# temperature.net
KiCad netlist of a schematic drawn in Altium Designer
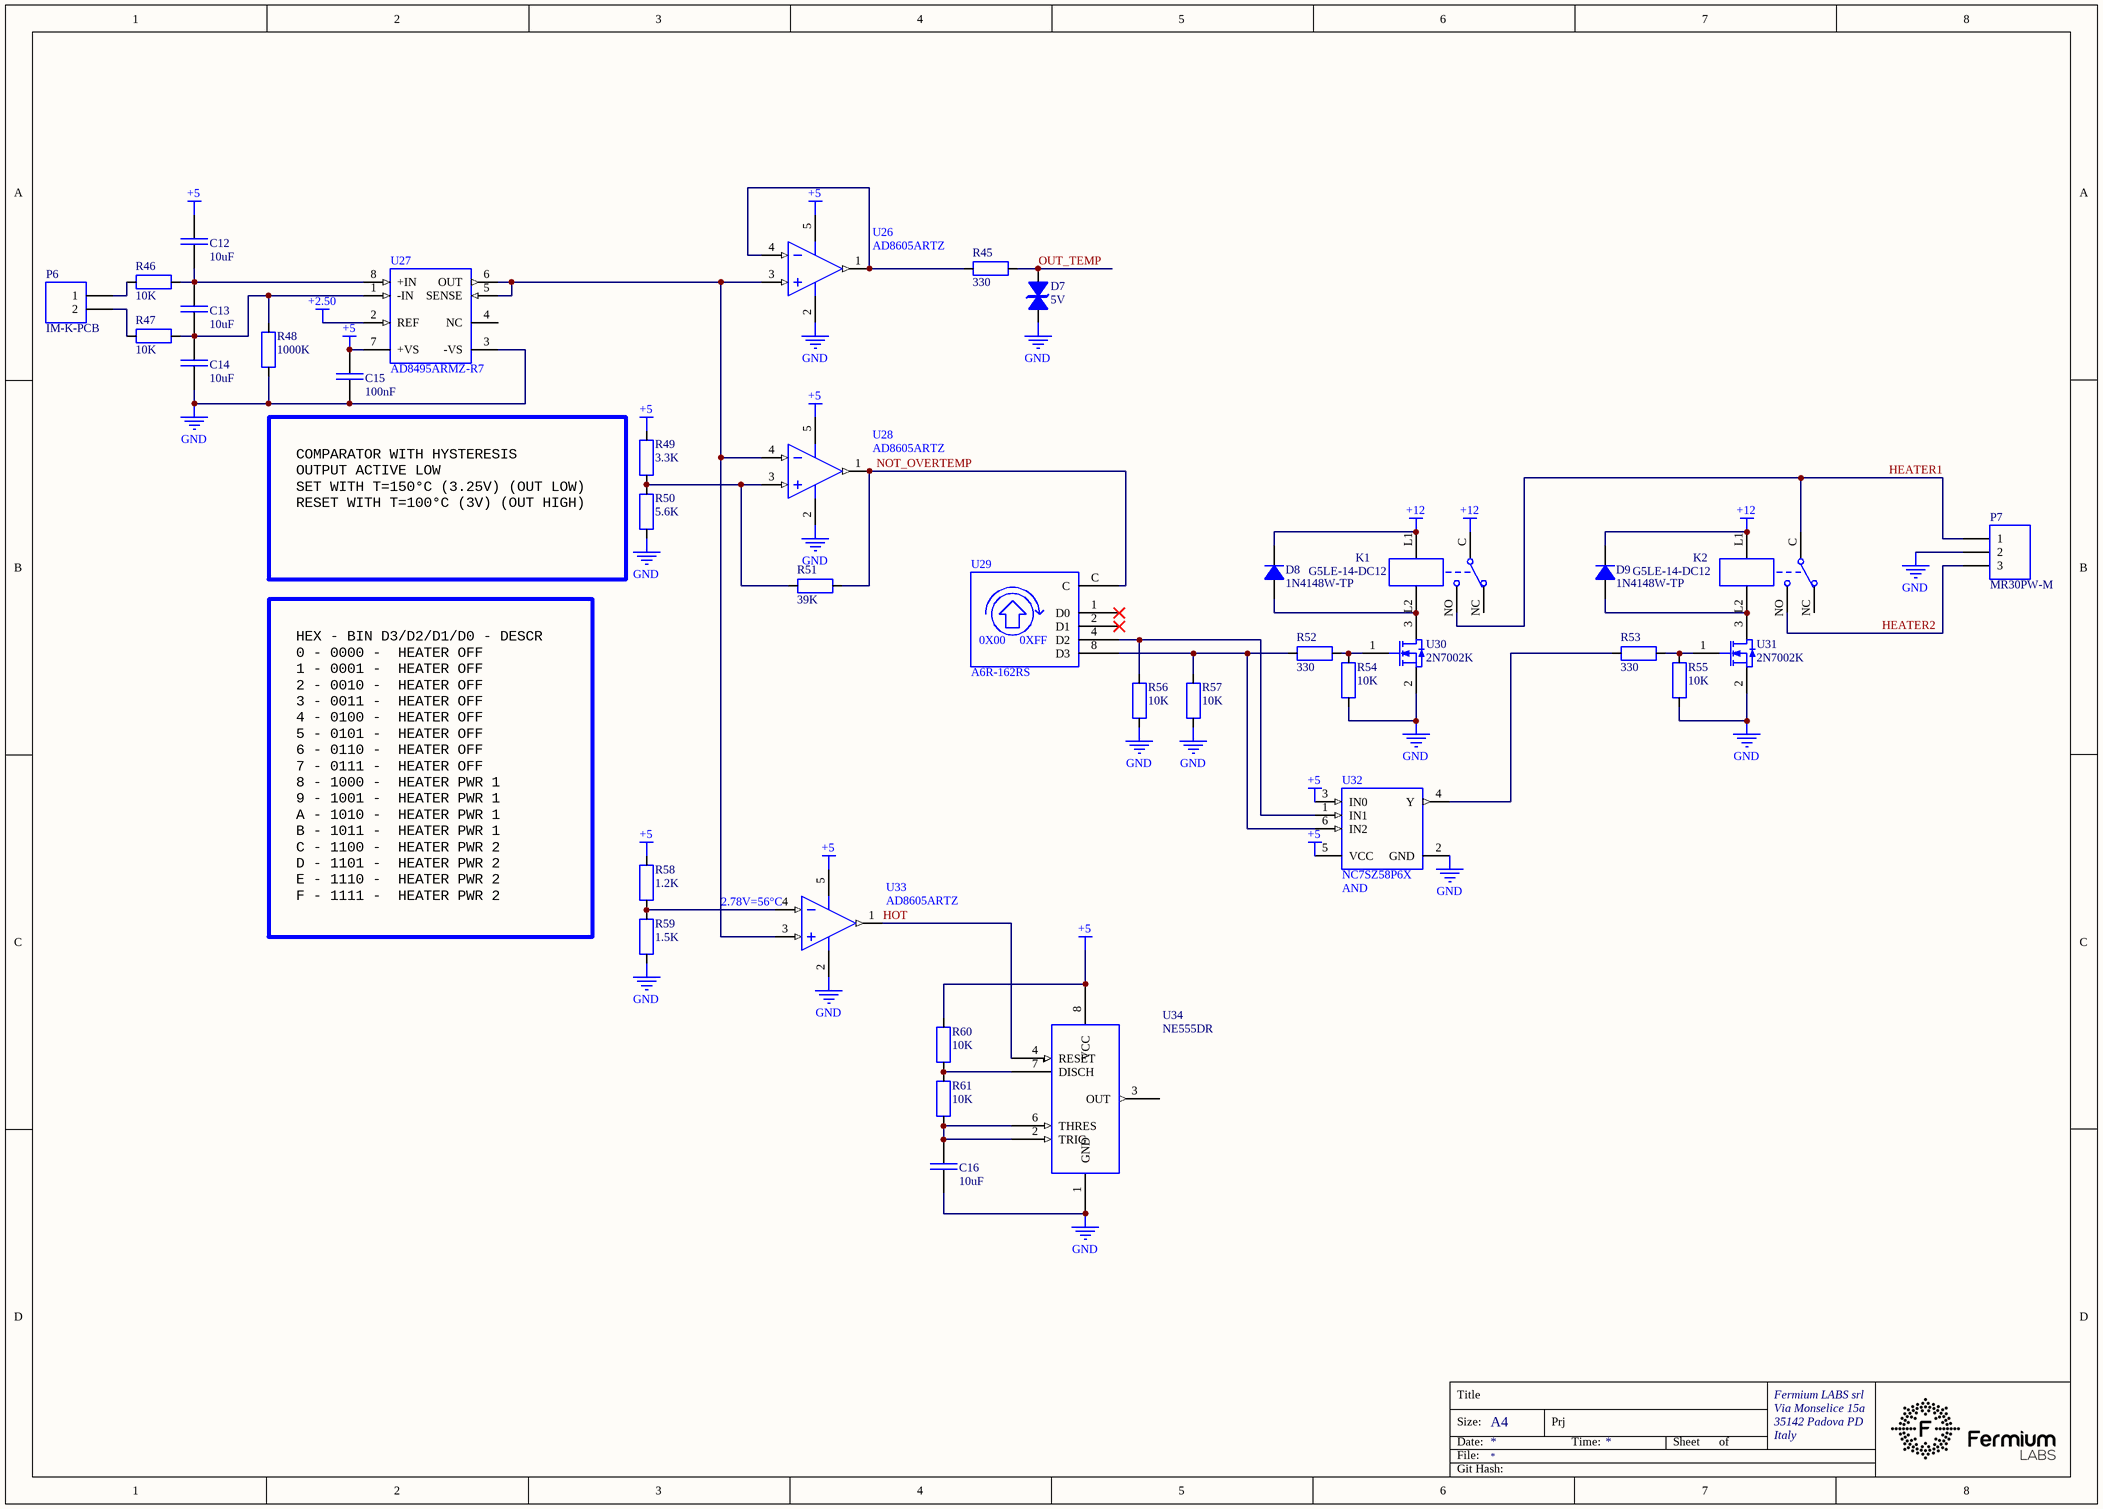
[diagram p0: temperature.SchDoc]

(export (version "E")
  (design (tool "Eeschema 10.0.6"))
  (components
    (comp (ref "C12")
      (value "10uF")
      (footprint "CAP 0805_2012")
      (description "CAP SMD MLCC 10uF 25V 0805 X5R")
      (fields (field (name "PART NUMBER") "1ffbe5a9-0884-4740-bdad-20a6a98400e6"))
      (libsource (lib "frmdblib") (part "GENERIC_C"))
    )
    (comp (ref "C13")
      (value "10uF")
      (footprint "CAP 0805_2012")
      (description "CAP SMD MLCC 10uF 25V 0805 X5R")
      (fields (field (name "PART NUMBER") "1ffbe5a9-0884-4740-bdad-20a6a98400e6"))
      (libsource (lib "frmdblib") (part "GENERIC_C"))
    )
    (comp (ref "C14")
      (value "10uF")
      (footprint "CAP 0805_2012")
      (description "CAP SMD MLCC 10uF 25V 0805 X5R")
      (fields (field (name "PART NUMBER") "1ffbe5a9-0884-4740-bdad-20a6a98400e6"))
      (libsource (lib "frmdblib") (part "GENERIC_C"))
    )
    (comp (ref "C15")
      (value "100nF")
      (footprint "CAP 0603_1608")
      (description "CAP SMD MLCC 100nF 25V 0603 X7R")
      (fields (field (name "PART NUMBER") "02841f84-ac15-41b5-9e17-915f8f067828"))
      (libsource (lib "frmdblib") (part "GENERIC_C"))
    )
    (comp (ref "C16")
      (value "10uF")
      (footprint "CAP 0805_2012")
      (description "CAP SMD MLCC 10uF 25V 0805 X5R")
      (fields (field (name "PART NUMBER") "1ffbe5a9-0884-4740-bdad-20a6a98400e6"))
      (libsource (lib "frmdblib") (part "GENERIC_C"))
    )
    (comp (ref "D7")
      (value "5V")
      (footprint "SOD523F")
      (description "DIODE SMD TVS 5V BIDIRECTIONAL SOD-523")
      (fields (field (name "PART NUMBER") "daa58212-38e2-4326-a156-8e48058c46f1"))
      (libsource (lib "frmdblib") (part "GENERIC_D_TVS_BI"))
    )
    (comp (ref "D8")
      (value "1N4148W-TP")
      (footprint "SOD-123")
      (description "DIODE SMD 100V 150mA 1.5Vf SOD-123 4148")
      (fields (field (name "PART NUMBER") "5e920700-75df-48e3-84dd-8f9f777caed8"))
      (libsource (lib "frmdblib") (part "GENERIC_D"))
    )
    (comp (ref "D9")
      (value "1N4148W-TP")
      (footprint "SOD-123")
      (description "DIODE SMD 100V 150mA 1.5Vf SOD-123 4148")
      (fields (field (name "PART NUMBER") "5e920700-75df-48e3-84dd-8f9f777caed8"))
      (libsource (lib "frmdblib") (part "GENERIC_D"))
    )
    (comp (ref "K1")
      (value "G5LE-14-DC12")
      (footprint "AAE46D0F-8D2F-4914-8614-C04E242B4758")
      (description "RELAY SPDT 10A 250VAC 12VDC SUBMINIATURE")
      (fields (field (name "PART NUMBER") "daf6f3cd-58c4-4886-bcb7-b7b47a76ae08"))
      (libsource (lib "frmdblib") (part "GENERIC_RELAY_SPDT"))
    )
    (comp (ref "K2")
      (value "G5LE-14-DC12")
      (footprint "AAE46D0F-8D2F-4914-8614-C04E242B4758")
      (description "RELAY SPDT 10A 250VAC 12VDC SUBMINIATURE")
      (fields (field (name "PART NUMBER") "daf6f3cd-58c4-4886-bcb7-b7b47a76ae08"))
      (libsource (lib "frmdblib") (part "GENERIC_RELAY_SPDT"))
    )
    (comp (ref "P6")
      (value "IM-K-PCB")
      (footprint "9044FB30-693E-4780-9B0B-95C5421D70E8")
      (description "CONN THERMOCOUPLE K-TYPE THT")
      (fields (field (name "PART NUMBER") "44088476-53fa-4578-a611-1fd63affe7b4"))
      (libsource (lib "frmdblib") (part "Header 2"))
    )
    (comp (ref "P7")
      (value "MR30PW-M")
      (footprint "B3F23392-877C-4EEC-B1AF-B260E8D92153")
      (description "CONN DC 3 POLE 15A PCB MALE")
      (fields (field (name "PART NUMBER") "8565bfd1-7a71-455a-a363-4ce9dda60de6"))
      (libsource (lib "frmdblib") (part "Header 3"))
    )
    (comp (ref "R45")
      (value "330")
      (description "RES SMD 330 OHM 1% 1/10W 0603")
      (fields (field (name "PART NUMBER") "e8555d7b-eeda-4727-b2e1-550cdc03d819"))
      (libsource (lib "frmdblib") (part "GENERIC_R"))
    )
    (comp (ref "R46")
      (value "10K")
      (footprint "RES 0603_1608")
      (description "RES SMD 10K OHM 1% 1/10W 0603")
      (fields (field (name "PART NUMBER") "93242766-ba1d-462d-b58f-ce1dfc4129c8"))
      (libsource (lib "frmdblib") (part "GENERIC_R"))
    )
    (comp (ref "R47")
      (value "10K")
      (footprint "RES 0603_1608")
      (description "RES SMD 10K OHM 1% 1/10W 0603")
      (fields (field (name "PART NUMBER") "93242766-ba1d-462d-b58f-ce1dfc4129c8"))
      (libsource (lib "frmdblib") (part "GENERIC_R"))
    )
    (comp (ref "R48")
      (value "1000K")
      (description "RES SMD 1000K OHM 1% 1/8W 0805")
      (fields (field (name "PART NUMBER") "971a2486-fdc6-42b3-9467-9814f305537f"))
      (libsource (lib "frmdblib") (part "GENERIC_R"))
    )
    (comp (ref "R49")
      (value "3.3K")
      (description "RES SMD 3.3K OHM 1% 1/10W 0603")
      (fields (field (name "PART NUMBER") "c685e076-af25-4fed-81c8-3eb7c43f01b8"))
      (libsource (lib "frmdblib") (part "GENERIC_R"))
    )
    (comp (ref "R50")
      (value "5.6K")
      (description "RES SMD 5.6K OHM 1% 1/10W 0603")
      (fields (field (name "PART NUMBER") "afc45e5f-a770-4ee7-b734-99356076b47f"))
      (libsource (lib "frmdblib") (part "GENERIC_R"))
    )
    (comp (ref "R51")
      (value "39K")
      (description "RES SMD 39K OHM 1% 1/10W 0603")
      (fields (field (name "PART NUMBER") "10a824dc-98f1-41df-91f2-219e0508d035"))
      (libsource (lib "frmdblib") (part "GENERIC_R"))
    )
    (comp (ref "R52")
      (value "330")
      (description "RES SMD 330 OHM 1% 1/10W 0603")
      (fields (field (name "PART NUMBER") "e8555d7b-eeda-4727-b2e1-550cdc03d819"))
      (libsource (lib "frmdblib") (part "GENERIC_R"))
    )
    (comp (ref "R53")
      (value "330")
      (description "RES SMD 330 OHM 1% 1/10W 0603")
      (fields (field (name "PART NUMBER") "e8555d7b-eeda-4727-b2e1-550cdc03d819"))
      (libsource (lib "frmdblib") (part "GENERIC_R"))
    )
    (comp (ref "R54")
      (value "10K")
      (footprint "RES 0603_1608")
      (description "RES SMD 10K OHM 1% 1/10W 0603")
      (fields (field (name "PART NUMBER") "93242766-ba1d-462d-b58f-ce1dfc4129c8"))
      (libsource (lib "frmdblib") (part "GENERIC_R"))
    )
    (comp (ref "R55")
      (value "10K")
      (footprint "RES 0603_1608")
      (description "RES SMD 10K OHM 1% 1/10W 0603")
      (fields (field (name "PART NUMBER") "93242766-ba1d-462d-b58f-ce1dfc4129c8"))
      (libsource (lib "frmdblib") (part "GENERIC_R"))
    )
    (comp (ref "R56")
      (value "10K")
      (footprint "RES 0603_1608")
      (description "RES SMD 10K OHM 1% 1/10W 0603")
      (fields (field (name "PART NUMBER") "93242766-ba1d-462d-b58f-ce1dfc4129c8"))
      (libsource (lib "frmdblib") (part "GENERIC_R"))
    )
    (comp (ref "R57")
      (value "10K")
      (footprint "RES 0603_1608")
      (description "RES SMD 10K OHM 1% 1/10W 0603")
      (fields (field (name "PART NUMBER") "93242766-ba1d-462d-b58f-ce1dfc4129c8"))
      (libsource (lib "frmdblib") (part "GENERIC_R"))
    )
    (comp (ref "R58")
      (value "1.2K")
      (description "RES SMD 1.2K OHM 1% 1/10W 0603")
      (fields (field (name "PART NUMBER") "2f6201d5-48c6-41ab-ab40-2cc6255291b8"))
      (libsource (lib "frmdblib") (part "GENERIC_R"))
    )
    (comp (ref "R59")
      (value "1.5K")
      (description "RES SMD 1.5K OHM 1% 1/10W 0603")
      (fields (field (name "PART NUMBER") "d098bc01-c90d-4b51-91ee-1d9d1ccd8970"))
      (libsource (lib "frmdblib") (part "GENERIC_R"))
    )
    (comp (ref "R60")
      (value "10K")
      (footprint "RES 0603_1608")
      (description "RES SMD 10K OHM 1% 1/10W 0603")
      (fields (field (name "PART NUMBER") "93242766-ba1d-462d-b58f-ce1dfc4129c8"))
      (libsource (lib "frmdblib") (part "GENERIC_R"))
    )
    (comp (ref "R61")
      (value "10K")
      (footprint "RES 0603_1608")
      (description "RES SMD 10K OHM 1% 1/10W 0603")
      (fields (field (name "PART NUMBER") "93242766-ba1d-462d-b58f-ce1dfc4129c8"))
      (libsource (lib "frmdblib") (part "GENERIC_R"))
    )
    (comp (ref "U26")
      (value "AD8605ARTZ")
      (footprint "A3DDA0BC-073E-4B18-9613-F713A7EC1E27")
      (description "IC OPAMP 65uV 1pA RRIO 5V 80mA SOT-23-5")
      (fields (field (name "PART NUMBER") "5610e9ea-bca8-49b2-8e5f-11409231f6a4"))
      (libsource (lib "frmdblib") (part "8096D751-9DCE-401B-B65E-AAEE0733EA70"))
    )
    (comp (ref "U27")
      (value "AD8495ARMZ-R7")
      (footprint "ANALOG MSOP-8 RM-8")
      (description "IC THERMOCOUPLE AMPLIFIER MSOP-8")
      (fields (field (name "PART NUMBER") "8cc7f909-42c7-4251-909a-43740f41a1ca"))
      (libsource (lib "frmdblib") (part "8E2A16B8-3194-4245-8B24-4BAEF980A7F4"))
    )
    (comp (ref "U28")
      (value "AD8605ARTZ")
      (footprint "A3DDA0BC-073E-4B18-9613-F713A7EC1E27")
      (description "IC OPAMP 65uV 1pA RRIO 5V 80mA SOT-23-5")
      (fields (field (name "PART NUMBER") "5610e9ea-bca8-49b2-8e5f-11409231f6a4"))
      (libsource (lib "frmdblib") (part "8096D751-9DCE-401B-B65E-AAEE0733EA70"))
    )
    (comp (ref "U29")
      (value "A6R-162RS")
      (footprint "2599C238-5645-4A8C-8BF9-C7515FACCFA0")
      (description "SWITCH ROTARY HEX/BCD 16 POSITIONS")
      (fields (field (name "PART NUMBER") "bbf157ad-cd7a-4e82-97e3-d6a037590888"))
      (libsource (lib "frmdblib") (part "EFC705A0-D700-486A-81AB-6EE045EE6C24"))
    )
    (comp (ref "U30")
      (value "2N7002K")
      (footprint "ON SEMI SOT-23-3")
      (description "MOSFET N-CHANNEL LOGIC LEVEL 300mA 3ohm 60V ESD-PROT 2N7002K SOT-23")
      (fields (field (name "PART NUMBER") "3a318f0a-3b94-47d9-91d5-8fc0a2f410e8"))
      (libsource (lib "frmdblib") (part "GENERIC_N_MOSFET_GSD"))
    )
    (comp (ref "U31")
      (value "2N7002K")
      (footprint "ON SEMI SOT-23-3")
      (description "MOSFET N-CHANNEL LOGIC LEVEL 300mA 3ohm 60V ESD-PROT 2N7002K SOT-23")
      (fields (field (name "PART NUMBER") "3a318f0a-3b94-47d9-91d5-8fc0a2f410e8"))
      (libsource (lib "frmdblib") (part "GENERIC_N_MOSFET_GSD"))
    )
    (comp (ref "U32")
      (value "NC7SZ58P6X")
      (footprint "CF792C6F-51F3-4C59-9918-AD84EFC14FA6")
      (description "IC LOGIC PORT CONFIGURABLE AND, OR, NAND, NOR, XOR, BUFFER, NOT 8ns  74XX58 SC-70")
      (fields (field (name "PART NUMBER") "22da43c7-1950-42f4-bc93-10d9cca79b4d"))
      (libsource (lib "frmdblib") (part "77922C7C-4696-4818-A68A-CF4581C7C2E9"))
    )
    (comp (ref "U33")
      (value "AD8605ARTZ")
      (footprint "A3DDA0BC-073E-4B18-9613-F713A7EC1E27")
      (description "IC OPAMP 65uV 1pA RRIO 5V 80mA SOT-23-5")
      (fields (field (name "PART NUMBER") "5610e9ea-bca8-49b2-8e5f-11409231f6a4"))
      (libsource (lib "frmdblib") (part "8096D751-9DCE-401B-B65E-AAEE0733EA70"))
    )
    (comp (ref "U34")
      (value "NE555DR")
      (footprint "TI SOIC-8 D")
      (description "IC SMD TIMER NE555 SOIC-8")
      (fields (field (name "PART NUMBER") "d16ab88a-2543-469a-8940-7b800b633548"))
      (libsource (lib "frmdblib") (part "3A1FF759-9FC3-4379-AD1F-76F749A75FB1"))
    )
  )
  (nets
    (net (code "1") (name "+2.50") (class "Default")
      (node (ref "U27") (pin "2") (pinfunction "REF_2") (pintype "input"))
    )
    (net (code "2") (name "+5") (class "Default")
      (node (ref "C12") (pin "2") (pintype "passive"))
      (node (ref "C15") (pin "1") (pintype "passive"))
      (node (ref "R49") (pin "2") (pintype "passive"))
      (node (ref "R58") (pin "2") (pintype "passive"))
      (node (ref "R60") (pin "2") (pintype "passive"))
      (node (ref "U26") (pin "5") (pinfunction "+V_5") (pintype "power_in"))
      (node (ref "U27") (pin "7") (pinfunction "+VS_7") (pintype "power_in"))
      (node (ref "U28") (pin "5") (pinfunction "+V_5") (pintype "power_in"))
      (node (ref "U32") (pin "3") (pinfunction "IN0_3") (pintype "input"))
      (node (ref "U32") (pin "5") (pinfunction "VCC_5") (pintype "power_in"))
      (node (ref "U33") (pin "5") (pinfunction "+V_5") (pintype "power_in"))
      (node (ref "U34") (pin "8") (pinfunction "VCC_8") (pintype "power_in"))
    )
    (net (code "3") (name "+12") (class "Default")
      (node (ref "D8") (pin "1") (pinfunction "K_1") (pintype "passive"))
      (node (ref "D9") (pin "1") (pinfunction "K_1") (pintype "passive"))
      (node (ref "K1") (pin "C") (pinfunction "C_C") (pintype "passive"))
      (node (ref "K1") (pin "L1") (pinfunction "L1_L1") (pintype "passive"))
      (node (ref "K2") (pin "L1") (pinfunction "L1_L1") (pintype "passive"))
    )
    (net (code "4") (name "/HEATER1") (class "Default")
      (node (ref "K1") (pin "NO") (pinfunction "NO_NO") (pintype "passive"))
      (node (ref "K2") (pin "C") (pinfunction "C_C") (pintype "passive"))
      (node (ref "P7") (pin "1") (pinfunction "1_1") (pintype "passive"))
    )
    (net (code "5") (name "/HEATER2") (class "Default")
      (node (ref "K2") (pin "NO") (pinfunction "NO_NO") (pintype "passive"))
      (node (ref "P7") (pin "3") (pinfunction "3_3") (pintype "passive"))
    )
    (net (code "6") (name "/HOT") (class "Default")
      (node (ref "U33") (pin "1") (pinfunction "OUT_1") (pintype "output"))
      (node (ref "U34") (pin "4") (pinfunction "RESET_4") (pintype "input"))
    )
    (net (code "7") (name "/NOT_OVERTEMP") (class "Default")
      (node (ref "R51") (pin "2") (pintype "passive"))
      (node (ref "U28") (pin "1") (pinfunction "OUT_1") (pintype "output"))
      (node (ref "U29") (pin "C") (pinfunction "C_C") (pintype "passive"))
    )
    (net (code "8") (name "/OUT_TEMP") (class "Default")
      (node (ref "D7") (pin "1") (pintype "passive"))
      (node (ref "R45") (pin "2") (pintype "passive"))
    )
    (net (code "9") (name "GND") (class "Default")
      (node (ref "C14") (pin "1") (pintype "passive"))
      (node (ref "C15") (pin "2") (pintype "passive"))
      (node (ref "C16") (pin "1") (pintype "passive"))
      (node (ref "D7") (pin "2") (pintype "passive"))
      (node (ref "P7") (pin "2") (pinfunction "2_2") (pintype "passive"))
      (node (ref "R48") (pin "1") (pintype "passive"))
      (node (ref "R50") (pin "1") (pintype "passive"))
      (node (ref "R54") (pin "1") (pintype "passive"))
      (node (ref "R55") (pin "1") (pintype "passive"))
      (node (ref "R56") (pin "1") (pintype "passive"))
      (node (ref "R57") (pin "1") (pintype "passive"))
      (node (ref "R59") (pin "1") (pintype "passive"))
      (node (ref "U26") (pin "2") (pinfunction "-V_2") (pintype "power_in"))
      (node (ref "U27") (pin "3") (pinfunction "-VS_3") (pintype "power_in"))
      (node (ref "U28") (pin "2") (pinfunction "-V_2") (pintype "power_in"))
      (node (ref "U30") (pin "2") (pinfunction "S_2") (pintype "passive"))
      (node (ref "U31") (pin "2") (pinfunction "S_2") (pintype "passive"))
      (node (ref "U32") (pin "2") (pinfunction "GND_2") (pintype "power_in"))
      (node (ref "U33") (pin "2") (pinfunction "-V_2") (pintype "power_in"))
      (node (ref "U34") (pin "1") (pinfunction "GND_1") (pintype "power_in"))
    )
    (net (code "10") (name "Net-(D8-A)") (class "Default")
      (node (ref "D8") (pin "2") (pinfunction "A_2") (pintype "passive"))
      (node (ref "K1") (pin "L2") (pinfunction "L2_L2") (pintype "passive"))
      (node (ref "U30") (pin "3") (pinfunction "D_3") (pintype "passive"))
    )
    (net (code "11") (name "Net-(D9-A)") (class "Default")
      (node (ref "D9") (pin "2") (pinfunction "A_2") (pintype "passive"))
      (node (ref "K2") (pin "L2") (pinfunction "L2_L2") (pintype "passive"))
      (node (ref "U31") (pin "3") (pinfunction "D_3") (pintype "passive"))
    )
    (net (code "12") (name "Net-(P6-Pad1)") (class "Default")
      (node (ref "P6") (pin "1") (pinfunction "1_1") (pintype "passive"))
      (node (ref "R46") (pin "2") (pintype "passive"))
    )
    (net (code "13") (name "Net-(P6-Pad2)") (class "Default")
      (node (ref "P6") (pin "2") (pinfunction "2_2") (pintype "passive"))
      (node (ref "R47") (pin "2") (pintype "passive"))
    )
    (net (code "14") (name "Net-(U26-+IN)") (class "Default")
      (node (ref "U26") (pin "3") (pinfunction "+IN_3") (pintype "input"))
      (node (ref "U27") (pin "5") (pinfunction "SENSE_5") (pintype "input"))
      (node (ref "U27") (pin "6") (pinfunction "OUT_6") (pintype "output"))
      (node (ref "U28") (pin "4") (pinfunction "-IN_4") (pintype "input"))
      (node (ref "U33") (pin "3") (pinfunction "+IN_3") (pintype "input"))
    )
    (net (code "15") (name "Net-(U26--IN)") (class "Default")
      (node (ref "R45") (pin "1") (pintype "passive"))
      (node (ref "U26") (pin "1") (pinfunction "OUT_1") (pintype "output"))
      (node (ref "U26") (pin "4") (pinfunction "-IN_4") (pintype "input"))
    )
    (net (code "16") (name "Net-(U27-+IN)") (class "Default")
      (node (ref "C12") (pin "1") (pintype "passive"))
      (node (ref "C13") (pin "2") (pintype "passive"))
      (node (ref "R46") (pin "1") (pintype "passive"))
      (node (ref "U27") (pin "8") (pinfunction "+IN_8") (pintype "input"))
    )
    (net (code "17") (name "Net-(U27--IN)") (class "Default")
      (node (ref "C13") (pin "1") (pintype "passive"))
      (node (ref "C14") (pin "2") (pintype "passive"))
      (node (ref "R47") (pin "1") (pintype "passive"))
      (node (ref "R48") (pin "2") (pintype "passive"))
      (node (ref "U27") (pin "1") (pinfunction "-IN_1") (pintype "input"))
    )
    (net (code "18") (name "Net-(U28-+IN)") (class "Default")
      (node (ref "R49") (pin "1") (pintype "passive"))
      (node (ref "R50") (pin "2") (pintype "passive"))
      (node (ref "R51") (pin "1") (pintype "passive"))
      (node (ref "U28") (pin "3") (pinfunction "+IN_3") (pintype "input"))
    )
    (net (code "19") (name "Net-(U29-D2)") (class "Default")
      (node (ref "R56") (pin "2") (pintype "passive"))
      (node (ref "U29") (pin "4") (pinfunction "D2_4") (pintype "passive"))
      (node (ref "U32") (pin "1") (pinfunction "IN1_1") (pintype "input"))
    )
    (net (code "20") (name "Net-(U29-D3)") (class "Default")
      (node (ref "R52") (pin "1") (pintype "passive"))
      (node (ref "R57") (pin "2") (pintype "passive"))
      (node (ref "U29") (pin "8") (pinfunction "D3_8") (pintype "passive"))
      (node (ref "U32") (pin "6") (pinfunction "IN2_6") (pintype "input"))
    )
    (net (code "21") (name "Net-(U30-G)") (class "Default")
      (node (ref "R52") (pin "2") (pintype "passive"))
      (node (ref "R54") (pin "2") (pintype "passive"))
      (node (ref "U30") (pin "1") (pinfunction "G_1") (pintype "passive"))
    )
    (net (code "22") (name "Net-(U31-G)") (class "Default")
      (node (ref "R53") (pin "2") (pintype "passive"))
      (node (ref "R55") (pin "2") (pintype "passive"))
      (node (ref "U31") (pin "1") (pinfunction "G_1") (pintype "passive"))
    )
    (net (code "23") (name "Net-(U32-Y)") (class "Default")
      (node (ref "R53") (pin "1") (pintype "passive"))
      (node (ref "U32") (pin "4") (pinfunction "Y_4") (pintype "output"))
    )
    (net (code "24") (name "Net-(U33--IN)") (class "Default")
      (node (ref "R58") (pin "1") (pintype "passive"))
      (node (ref "R59") (pin "2") (pintype "passive"))
      (node (ref "U33") (pin "4") (pinfunction "-IN_4") (pintype "input"))
    )
    (net (code "25") (name "Net-(U34-DISCH)") (class "Default")
      (node (ref "R60") (pin "1") (pintype "passive"))
      (node (ref "R61") (pin "2") (pintype "passive"))
      (node (ref "U34") (pin "7") (pinfunction "DISCH_7") (pintype "passive"))
    )
    (net (code "26") (name "Net-(U34-THRES)") (class "Default")
      (node (ref "C16") (pin "2") (pintype "passive"))
      (node (ref "R61") (pin "1") (pintype "passive"))
      (node (ref "U34") (pin "2") (pinfunction "TRIG_2") (pintype "input"))
      (node (ref "U34") (pin "6") (pinfunction "THRES_6") (pintype "input"))
    )
    (net (code "27") (name "unconnected-(K1-PadNC)") (class "Default")
      (node (ref "K1") (pin "NC") (pinfunction "NC_NC") (pintype "passive"))
    )
    (net (code "28") (name "unconnected-(K2-PadNC)") (class "Default")
      (node (ref "K2") (pin "NC") (pinfunction "NC_NC") (pintype "passive"))
    )
    (net (code "29") (name "unconnected-(U27-NC-Pad4)") (class "Default")
      (node (ref "U27") (pin "4") (pinfunction "NC_4") (pintype "passive"))
    )
    (net (code "30") (name "unconnected-(U29-D0-Pad1)") (class "Default")
      (node (ref "U29") (pin "1") (pinfunction "D0_1") (pintype "passive+no_connect"))
    )
    (net (code "31") (name "unconnected-(U29-D1-Pad2)") (class "Default")
      (node (ref "U29") (pin "2") (pinfunction "D1_2") (pintype "passive+no_connect"))
    )
    (net (code "32") (name "unconnected-(U34-OUT-Pad3)") (class "Default")
      (node (ref "U34") (pin "3") (pinfunction "OUT_3") (pintype "output"))
    )
  )
)
